# CFO_nano_protoWithDACandOpAmpMCP4822.net
KiCad netlist of a schematic drawn in EAGLE
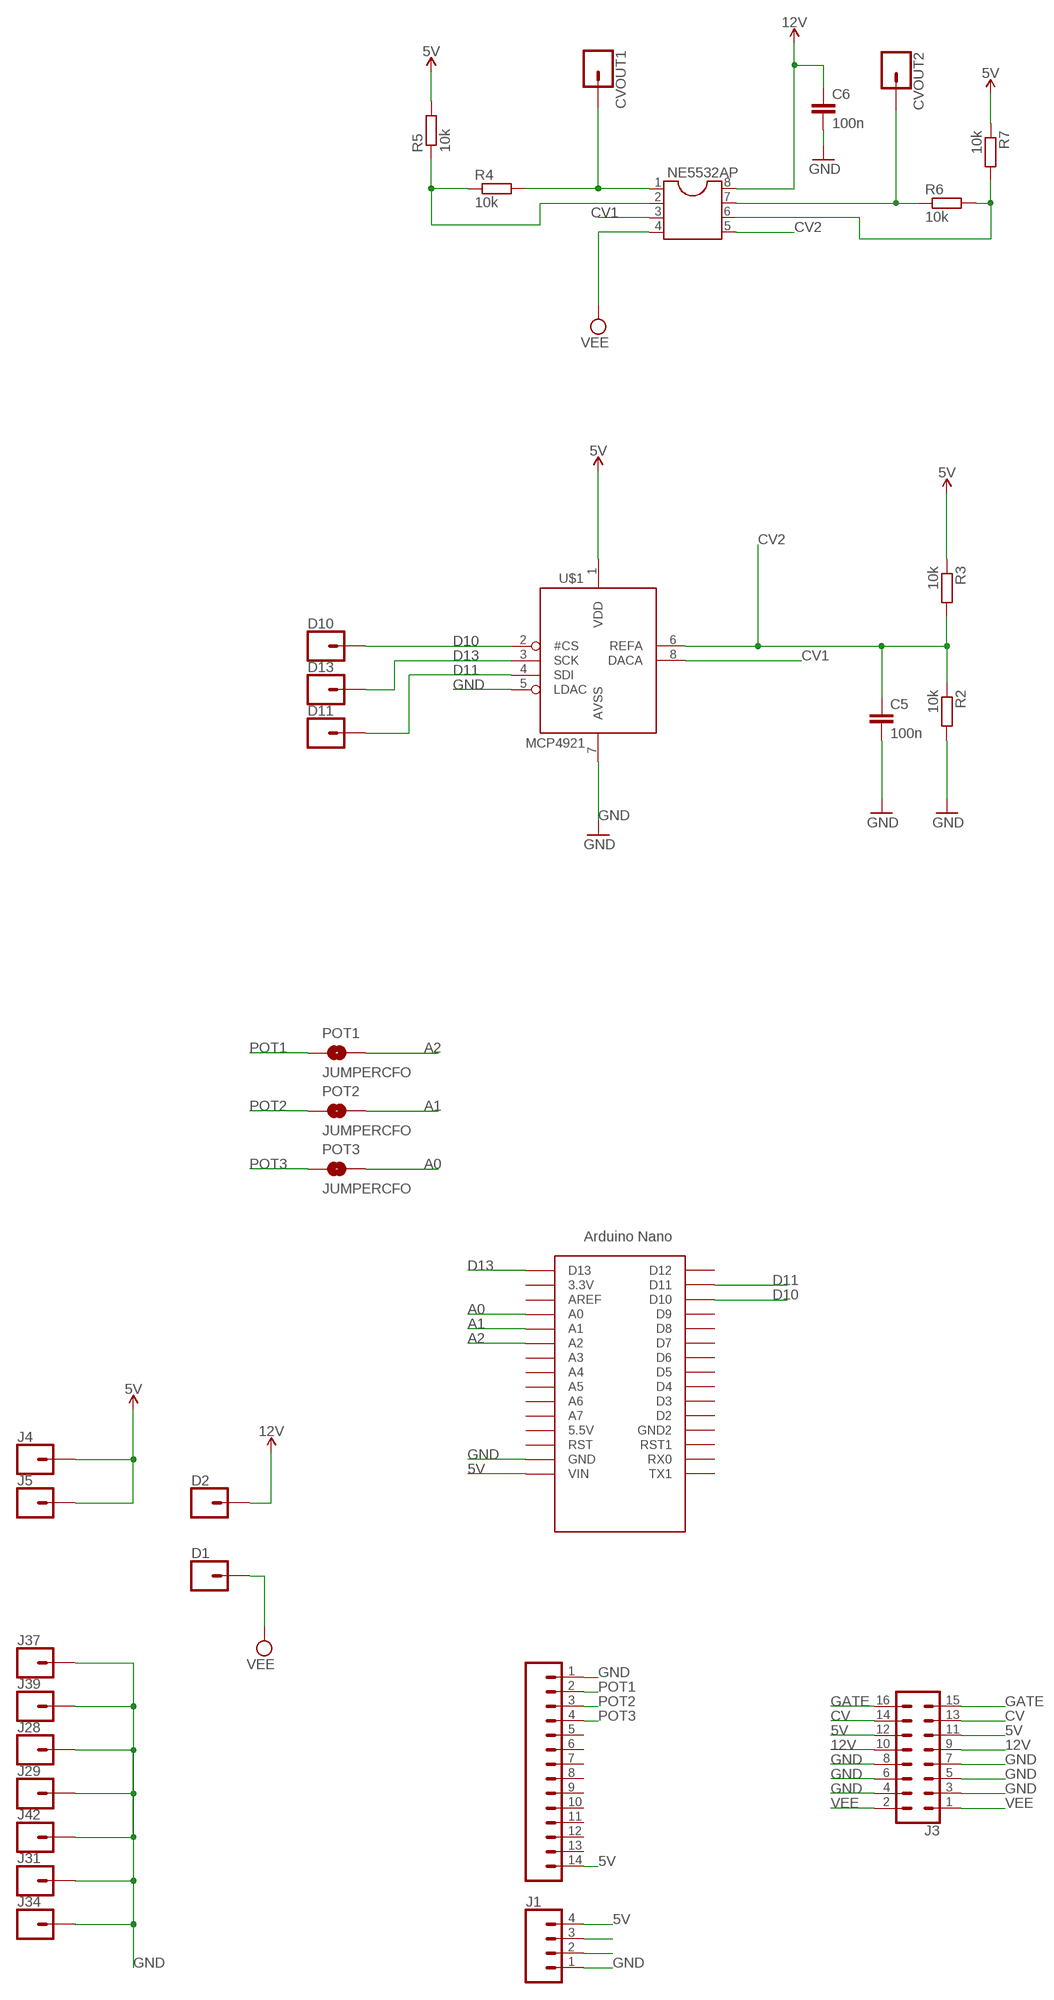
[diagram p0: schematic, sheet 1]

(export (version "E")
  (design (tool "Eeschema 10.0.6"))
  (components
    (comp (ref "C5")
      (value "100n")
      (footprint "eagle-import:C050-025X075")
      (libsource (lib "eagle-import") (part "C-EU050-025X075"))
    )
    (comp (ref "C6")
      (value "100n")
      (footprint "eagle-import:C050-025X075")
      (libsource (lib "eagle-import") (part "C-EU050-025X075"))
    )
    (comp (ref "CVOUT1")
      (value "CONN_01")
      (footprint "eagle-import:1X01")
      (libsource (lib "eagle-import") (part "CONN_01"))
    )
    (comp (ref "CVOUT2")
      (value "CONN_01")
      (footprint "eagle-import:1X01")
      (libsource (lib "eagle-import") (part "CONN_01"))
    )
    (comp (ref "D1")
      (value "CONN_01")
      (footprint "eagle-import:1X01")
      (libsource (lib "eagle-import") (part "CONN_01"))
    )
    (comp (ref "D2")
      (value "CONN_01")
      (footprint "eagle-import:1X01")
      (libsource (lib "eagle-import") (part "CONN_01"))
    )
    (comp (ref "D10")
      (value "CONN_01")
      (footprint "eagle-import:1X01")
      (libsource (lib "eagle-import") (part "CONN_01"))
    )
    (comp (ref "D11")
      (value "CONN_01")
      (footprint "eagle-import:1X01")
      (libsource (lib "eagle-import") (part "CONN_01"))
    )
    (comp (ref "D13")
      (value "CONN_01")
      (footprint "eagle-import:1X01")
      (libsource (lib "eagle-import") (part "CONN_01"))
    )
    (comp (ref "J1")
      (value "CONN_04")
      (footprint "eagle-import:1X04")
      (fields (field (name "SPICEPREFIX") "E"))
      (libsource (lib "eagle-import") (part "CONN_04"))
    )
    (comp (ref "J2")
      (value "CONN_14SQUARE")
      (footprint "eagle-import:1X14")
      (fields (field (name "SPICEPREFIX") "X"))
      (libsource (lib "eagle-import") (part "CONN_14SQUARE"))
    )
    (comp (ref "J3")
      (value "CONN_08X2_SHROUD")
      (footprint "eagle-import:2X8-SHROUDED_LOCK")
      (libsource (lib "eagle-import") (part "CONN_08X2_SHROUD"))
    )
    (comp (ref "J4")
      (value "CONN_01")
      (footprint "eagle-import:1X01")
      (libsource (lib "eagle-import") (part "CONN_01"))
    )
    (comp (ref "J5")
      (value "CONN_01")
      (footprint "eagle-import:1X01")
      (libsource (lib "eagle-import") (part "CONN_01"))
    )
    (comp (ref "J28")
      (value "CONN_01")
      (footprint "eagle-import:1X01")
      (libsource (lib "eagle-import") (part "CONN_01"))
    )
    (comp (ref "J29")
      (value "CONN_01")
      (footprint "eagle-import:1X01")
      (libsource (lib "eagle-import") (part "CONN_01"))
    )
    (comp (ref "J31")
      (value "CONN_01")
      (footprint "eagle-import:1X01")
      (libsource (lib "eagle-import") (part "CONN_01"))
    )
    (comp (ref "J34")
      (value "CONN_01")
      (footprint "eagle-import:1X01")
      (libsource (lib "eagle-import") (part "CONN_01"))
    )
    (comp (ref "J37")
      (value "CONN_01")
      (footprint "eagle-import:1X01")
      (libsource (lib "eagle-import") (part "CONN_01"))
    )
    (comp (ref "J39")
      (value "CONN_01")
      (footprint "eagle-import:1X01")
      (libsource (lib "eagle-import") (part "CONN_01"))
    )
    (comp (ref "J42")
      (value "CONN_01")
      (footprint "eagle-import:1X01")
      (libsource (lib "eagle-import") (part "CONN_01"))
    )
    (comp (ref "NE5532AP")
      (value "DIL8")
      (footprint "eagle-import:DIL08")
      (libsource (lib "eagle-import") (part "DIL8"))
    )
    (comp (ref "POT1")
      (value "JUMPERCFO")
      (footprint "eagle-import:SMT-JUMPER_2_NO_NO-SILK_ROUND")
      (libsource (lib "eagle-import") (part "JUMPERCFO"))
    )
    (comp (ref "POT2")
      (value "JUMPERCFO")
      (footprint "eagle-import:SMT-JUMPER_2_NO_NO-SILK_ROUND")
      (libsource (lib "eagle-import") (part "JUMPERCFO"))
    )
    (comp (ref "POT3")
      (value "JUMPERCFO")
      (footprint "eagle-import:SMT-JUMPER_2_NO_NO-SILK_ROUND")
      (libsource (lib "eagle-import") (part "JUMPERCFO"))
    )
    (comp (ref "R2")
      (value "10k")
      (footprint "eagle-import:0207_10")
      (libsource (lib "eagle-import") (part "R-EU_0207/10"))
    )
    (comp (ref "R3")
      (value "10k")
      (footprint "eagle-import:0207_10")
      (libsource (lib "eagle-import") (part "R-EU_0207/10"))
    )
    (comp (ref "R4")
      (value "10k")
      (footprint "eagle-import:0207_10")
      (libsource (lib "eagle-import") (part "R-EU_0207/10"))
    )
    (comp (ref "R5")
      (value "10k")
      (footprint "eagle-import:0207_10")
      (libsource (lib "eagle-import") (part "R-EU_0207/10"))
    )
    (comp (ref "R6")
      (value "10k")
      (footprint "eagle-import:0207_10")
      (libsource (lib "eagle-import") (part "R-EU_0207/10"))
    )
    (comp (ref "R7")
      (value "10k")
      (footprint "eagle-import:0207_10")
      (libsource (lib "eagle-import") (part "R-EU_0207/10"))
    )
    (comp (ref "U$1")
      (value "MCP4921")
      (footprint "eagle-import:DIL08")
      (libsource (lib "eagle-import") (part "MCP4921"))
    )
    (comp (ref "U$2")
      (value "NANO")
      (footprint "eagle-import:NANO")
      (libsource (lib "eagle-import") (part "NANO"))
    )
  )
  (nets
    (net (code "1") (name "/A0") (class "Default")
      (node (ref "POT3") (pin "2") (pinfunction "2_2") (pintype "passive"))
      (node (ref "U$2") (pin "A0") (pinfunction "A0_A0") (pintype "bidirectional"))
    )
    (net (code "2") (name "/A1") (class "Default")
      (node (ref "POT2") (pin "2") (pinfunction "2_2") (pintype "passive"))
      (node (ref "U$2") (pin "A1") (pinfunction "A1_A1") (pintype "bidirectional"))
    )
    (net (code "3") (name "/A2") (class "Default")
      (node (ref "POT1") (pin "2") (pinfunction "2_2") (pintype "passive"))
      (node (ref "U$2") (pin "A2") (pinfunction "A2_A2") (pintype "bidirectional"))
    )
    (net (code "4") (name "/CV") (class "Default")
      (node (ref "J3") (pin "13") (pinfunction "13_13") (pintype "passive"))
      (node (ref "J3") (pin "14") (pinfunction "14_14") (pintype "passive"))
    )
    (net (code "5") (name "/CV1") (class "Default")
      (node (ref "NE5532AP") (pin "3") (pinfunction "3_3") (pintype "passive"))
      (node (ref "U$1") (pin "8") (pinfunction "DACA_8") (pintype "output"))
    )
    (net (code "6") (name "/CV2") (class "Default")
      (node (ref "C5") (pin "1") (pinfunction "1_1") (pintype "passive"))
      (node (ref "NE5532AP") (pin "5") (pinfunction "5_5") (pintype "passive"))
      (node (ref "R2") (pin "1") (pinfunction "1_1") (pintype "passive"))
      (node (ref "R3") (pin "2") (pinfunction "2_2") (pintype "passive"))
      (node (ref "U$1") (pin "6") (pinfunction "REFA_6") (pintype "input"))
    )
    (net (code "7") (name "/D10") (class "Default")
      (node (ref "D10") (pin "1") (pinfunction "1_1") (pintype "passive"))
      (node (ref "U$1") (pin "2") (pinfunction "#CS_2") (pintype "input"))
      (node (ref "U$2") (pin "D10") (pinfunction "D10_D10") (pintype "bidirectional"))
    )
    (net (code "8") (name "/D11") (class "Default")
      (node (ref "D11") (pin "1") (pinfunction "1_1") (pintype "passive"))
      (node (ref "U$1") (pin "4") (pinfunction "SDI_4") (pintype "input"))
      (node (ref "U$2") (pin "D11") (pinfunction "D11_D11") (pintype "bidirectional"))
    )
    (net (code "9") (name "/D13") (class "Default")
      (node (ref "D13") (pin "1") (pinfunction "1_1") (pintype "passive"))
      (node (ref "U$1") (pin "3") (pinfunction "SCK_3") (pintype "input"))
      (node (ref "U$2") (pin "D13") (pinfunction "D13_D13") (pintype "bidirectional"))
    )
    (net (code "10") (name "/GATE") (class "Default")
      (node (ref "J3") (pin "15") (pinfunction "15_15") (pintype "passive"))
      (node (ref "J3") (pin "16") (pinfunction "16_16") (pintype "passive"))
    )
    (net (code "11") (name "/POT1") (class "Default")
      (node (ref "J2") (pin "2") (pinfunction "2_2") (pintype "passive"))
      (node (ref "POT1") (pin "1") (pinfunction "1_1") (pintype "passive"))
    )
    (net (code "12") (name "/POT2") (class "Default")
      (node (ref "J2") (pin "3") (pinfunction "3_3") (pintype "passive"))
      (node (ref "POT2") (pin "1") (pinfunction "1_1") (pintype "passive"))
    )
    (net (code "13") (name "/POT3") (class "Default")
      (node (ref "J2") (pin "4") (pinfunction "4_4") (pintype "passive"))
      (node (ref "POT3") (pin "1") (pinfunction "1_1") (pintype "passive"))
    )
    (net (code "14") (name "5V") (class "Default")
      (node (ref "J1") (pin "4") (pinfunction "4_4") (pintype "passive"))
      (node (ref "J2") (pin "14") (pinfunction "14_14") (pintype "passive"))
      (node (ref "J3") (pin "11") (pinfunction "11_11") (pintype "passive"))
      (node (ref "J3") (pin "12") (pinfunction "12_12") (pintype "passive"))
      (node (ref "J4") (pin "1") (pinfunction "1_1") (pintype "passive"))
      (node (ref "J5") (pin "1") (pinfunction "1_1") (pintype "passive"))
      (node (ref "R3") (pin "1") (pinfunction "1_1") (pintype "passive"))
      (node (ref "R5") (pin "2") (pinfunction "2_2") (pintype "passive"))
      (node (ref "R7") (pin "1") (pinfunction "1_1") (pintype "passive"))
      (node (ref "U$1") (pin "1") (pinfunction "VDD_1") (pintype "power_in"))
      (node (ref "U$2") (pin "VIN") (pinfunction "VIN_VIN") (pintype "bidirectional"))
    )
    (net (code "15") (name "12V") (class "Default")
      (node (ref "C6") (pin "1") (pinfunction "1_1") (pintype "passive"))
      (node (ref "D2") (pin "1") (pinfunction "1_1") (pintype "passive"))
      (node (ref "J3") (pin "10") (pinfunction "10_10") (pintype "passive"))
      (node (ref "J3") (pin "9") (pinfunction "9_9") (pintype "passive"))
      (node (ref "NE5532AP") (pin "8") (pinfunction "8_8") (pintype "passive"))
    )
    (net (code "16") (name "GND") (class "Default")
      (node (ref "C5") (pin "2") (pinfunction "2_2") (pintype "passive"))
      (node (ref "C6") (pin "2") (pinfunction "2_2") (pintype "passive"))
      (node (ref "J1") (pin "1") (pinfunction "1_1") (pintype "passive"))
      (node (ref "J2") (pin "1") (pinfunction "1_1") (pintype "passive"))
      (node (ref "J28") (pin "1") (pinfunction "1_1") (pintype "passive"))
      (node (ref "J29") (pin "1") (pinfunction "1_1") (pintype "passive"))
      (node (ref "J3") (pin "3") (pinfunction "3_3") (pintype "passive"))
      (node (ref "J3") (pin "4") (pinfunction "4_4") (pintype "passive"))
      (node (ref "J3") (pin "5") (pinfunction "5_5") (pintype "passive"))
      (node (ref "J3") (pin "6") (pinfunction "6_6") (pintype "passive"))
      (node (ref "J3") (pin "7") (pinfunction "7_7") (pintype "passive"))
      (node (ref "J3") (pin "8") (pinfunction "8_8") (pintype "passive"))
      (node (ref "J31") (pin "1") (pinfunction "1_1") (pintype "passive"))
      (node (ref "J34") (pin "1") (pinfunction "1_1") (pintype "passive"))
      (node (ref "J37") (pin "1") (pinfunction "1_1") (pintype "passive"))
      (node (ref "J39") (pin "1") (pinfunction "1_1") (pintype "passive"))
      (node (ref "J42") (pin "1") (pinfunction "1_1") (pintype "passive"))
      (node (ref "R2") (pin "2") (pinfunction "2_2") (pintype "passive"))
      (node (ref "U$1") (pin "5") (pinfunction "LDAC_5") (pintype "input"))
      (node (ref "U$1") (pin "7") (pinfunction "AVSS_7") (pintype "power_in"))
      (node (ref "U$2") (pin "GND") (pinfunction "GND_GND") (pintype "bidirectional"))
    )
    (net (code "17") (name "Net-(CVOUT1-Pad1)") (class "Default")
      (node (ref "CVOUT1") (pin "1") (pinfunction "1_1") (pintype "passive"))
      (node (ref "NE5532AP") (pin "1") (pinfunction "1_1") (pintype "passive"))
      (node (ref "R4") (pin "2") (pinfunction "2_2") (pintype "passive"))
    )
    (net (code "18") (name "Net-(CVOUT2-Pad1)") (class "Default")
      (node (ref "CVOUT2") (pin "1") (pinfunction "1_1") (pintype "passive"))
      (node (ref "NE5532AP") (pin "7") (pinfunction "7_7") (pintype "passive"))
      (node (ref "R6") (pin "1") (pinfunction "1_1") (pintype "passive"))
    )
    (net (code "19") (name "Net-(NE5532AP-Pad2)") (class "Default")
      (node (ref "NE5532AP") (pin "2") (pinfunction "2_2") (pintype "passive"))
      (node (ref "R4") (pin "1") (pinfunction "1_1") (pintype "passive"))
      (node (ref "R5") (pin "1") (pinfunction "1_1") (pintype "passive"))
    )
    (net (code "20") (name "Net-(NE5532AP-Pad6)") (class "Default")
      (node (ref "NE5532AP") (pin "6") (pinfunction "6_6") (pintype "passive"))
      (node (ref "R6") (pin "2") (pinfunction "2_2") (pintype "passive"))
      (node (ref "R7") (pin "2") (pinfunction "2_2") (pintype "passive"))
    )
    (net (code "21") (name "VEE") (class "Default")
      (node (ref "D1") (pin "1") (pinfunction "1_1") (pintype "passive"))
      (node (ref "J3") (pin "1") (pinfunction "1_1") (pintype "passive"))
      (node (ref "J3") (pin "2") (pinfunction "2_2") (pintype "passive"))
      (node (ref "NE5532AP") (pin "4") (pinfunction "4_4") (pintype "passive"))
    )
    (net (code "22") (name "unconnected-(J1-Pad2)") (class "Default")
      (node (ref "J1") (pin "2") (pinfunction "2_2") (pintype "passive"))
    )
    (net (code "23") (name "unconnected-(J1-Pad3)") (class "Default")
      (node (ref "J1") (pin "3") (pinfunction "3_3") (pintype "passive"))
    )
    (net (code "24") (name "unconnected-(J2-Pad5)") (class "Default")
      (node (ref "J2") (pin "5") (pinfunction "5_5") (pintype "passive"))
    )
    (net (code "25") (name "unconnected-(J2-Pad6)") (class "Default")
      (node (ref "J2") (pin "6") (pinfunction "6_6") (pintype "passive"))
    )
    (net (code "26") (name "unconnected-(J2-Pad7)") (class "Default")
      (node (ref "J2") (pin "7") (pinfunction "7_7") (pintype "passive"))
    )
    (net (code "27") (name "unconnected-(J2-Pad8)") (class "Default")
      (node (ref "J2") (pin "8") (pinfunction "8_8") (pintype "passive"))
    )
    (net (code "28") (name "unconnected-(J2-Pad9)") (class "Default")
      (node (ref "J2") (pin "9") (pinfunction "9_9") (pintype "passive"))
    )
    (net (code "29") (name "unconnected-(J2-Pad10)") (class "Default")
      (node (ref "J2") (pin "10") (pinfunction "10_10") (pintype "passive"))
    )
    (net (code "30") (name "unconnected-(J2-Pad11)") (class "Default")
      (node (ref "J2") (pin "11") (pinfunction "11_11") (pintype "passive"))
    )
    (net (code "31") (name "unconnected-(J2-Pad12)") (class "Default")
      (node (ref "J2") (pin "12") (pinfunction "12_12") (pintype "passive"))
    )
    (net (code "32") (name "unconnected-(J2-Pad13)") (class "Default")
      (node (ref "J2") (pin "13") (pinfunction "13_13") (pintype "passive"))
    )
    (net (code "33") (name "unconnected-(U$2-5.5V-Pad5V)") (class "Default")
      (node (ref "U$2") (pin "5V") (pinfunction "5.5V_5V") (pintype "bidirectional"))
    )
    (net (code "34") (name "unconnected-(U$2-GND2-PadGND1)") (class "Default")
      (node (ref "U$2") (pin "GND1") (pinfunction "GND2_GND1") (pintype "bidirectional"))
    )
    (net (code "35") (name "unconnected-(U$2-Pad3.3V)") (class "Default")
      (node (ref "U$2") (pin "3.3V") (pinfunction "3.3V_3.3V") (pintype "bidirectional"))
    )
    (net (code "36") (name "unconnected-(U$2-PadA3)") (class "Default")
      (node (ref "U$2") (pin "A3") (pinfunction "A3_A3") (pintype "bidirectional"))
    )
    (net (code "37") (name "unconnected-(U$2-PadA4)") (class "Default")
      (node (ref "U$2") (pin "A4") (pinfunction "A4_A4") (pintype "bidirectional"))
    )
    (net (code "38") (name "unconnected-(U$2-PadA5)") (class "Default")
      (node (ref "U$2") (pin "A5") (pinfunction "A5_A5") (pintype "bidirectional"))
    )
    (net (code "39") (name "unconnected-(U$2-PadA6)") (class "Default")
      (node (ref "U$2") (pin "A6") (pinfunction "A6_A6") (pintype "bidirectional"))
    )
    (net (code "40") (name "unconnected-(U$2-PadA7)") (class "Default")
      (node (ref "U$2") (pin "A7") (pinfunction "A7_A7") (pintype "bidirectional"))
    )
    (net (code "41") (name "unconnected-(U$2-PadAREF)") (class "Default")
      (node (ref "U$2") (pin "AREF") (pinfunction "AREF_AREF") (pintype "bidirectional"))
    )
    (net (code "42") (name "unconnected-(U$2-PadD2)") (class "Default")
      (node (ref "U$2") (pin "D2") (pinfunction "D2_D2") (pintype "bidirectional"))
    )
    (net (code "43") (name "unconnected-(U$2-PadD3)") (class "Default")
      (node (ref "U$2") (pin "D3") (pinfunction "D3_D3") (pintype "bidirectional"))
    )
    (net (code "44") (name "unconnected-(U$2-PadD4)") (class "Default")
      (node (ref "U$2") (pin "D4") (pinfunction "D4_D4") (pintype "bidirectional"))
    )
    (net (code "45") (name "unconnected-(U$2-PadD5)") (class "Default")
      (node (ref "U$2") (pin "D5") (pinfunction "D5_D5") (pintype "bidirectional"))
    )
    (net (code "46") (name "unconnected-(U$2-PadD6)") (class "Default")
      (node (ref "U$2") (pin "D6") (pinfunction "D6_D6") (pintype "bidirectional"))
    )
    (net (code "47") (name "unconnected-(U$2-PadD7)") (class "Default")
      (node (ref "U$2") (pin "D7") (pinfunction "D7_D7") (pintype "bidirectional"))
    )
    (net (code "48") (name "unconnected-(U$2-PadD8)") (class "Default")
      (node (ref "U$2") (pin "D8") (pinfunction "D8_D8") (pintype "bidirectional"))
    )
    (net (code "49") (name "unconnected-(U$2-PadD9)") (class "Default")
      (node (ref "U$2") (pin "D9") (pinfunction "D9_D9") (pintype "bidirectional"))
    )
    (net (code "50") (name "unconnected-(U$2-PadD12)") (class "Default")
      (node (ref "U$2") (pin "D12") (pinfunction "D12_D12") (pintype "bidirectional"))
    )
    (net (code "51") (name "unconnected-(U$2-PadRST)") (class "Default")
      (node (ref "U$2") (pin "RST") (pinfunction "RST_RST") (pintype "bidirectional"))
    )
    (net (code "52") (name "unconnected-(U$2-PadRST1)") (class "Default")
      (node (ref "U$2") (pin "RST1") (pinfunction "RST1_RST1") (pintype "bidirectional"))
    )
    (net (code "53") (name "unconnected-(U$2-PadRX0)") (class "Default")
      (node (ref "U$2") (pin "RX0") (pinfunction "RX0_RX0") (pintype "bidirectional"))
    )
    (net (code "54") (name "unconnected-(U$2-PadTX1)") (class "Default")
      (node (ref "U$2") (pin "TX1") (pinfunction "TX1_TX1") (pintype "bidirectional"))
    )
  )
)
